# pad3.net
KiCad netlist of a schematic drawn in EAGLE
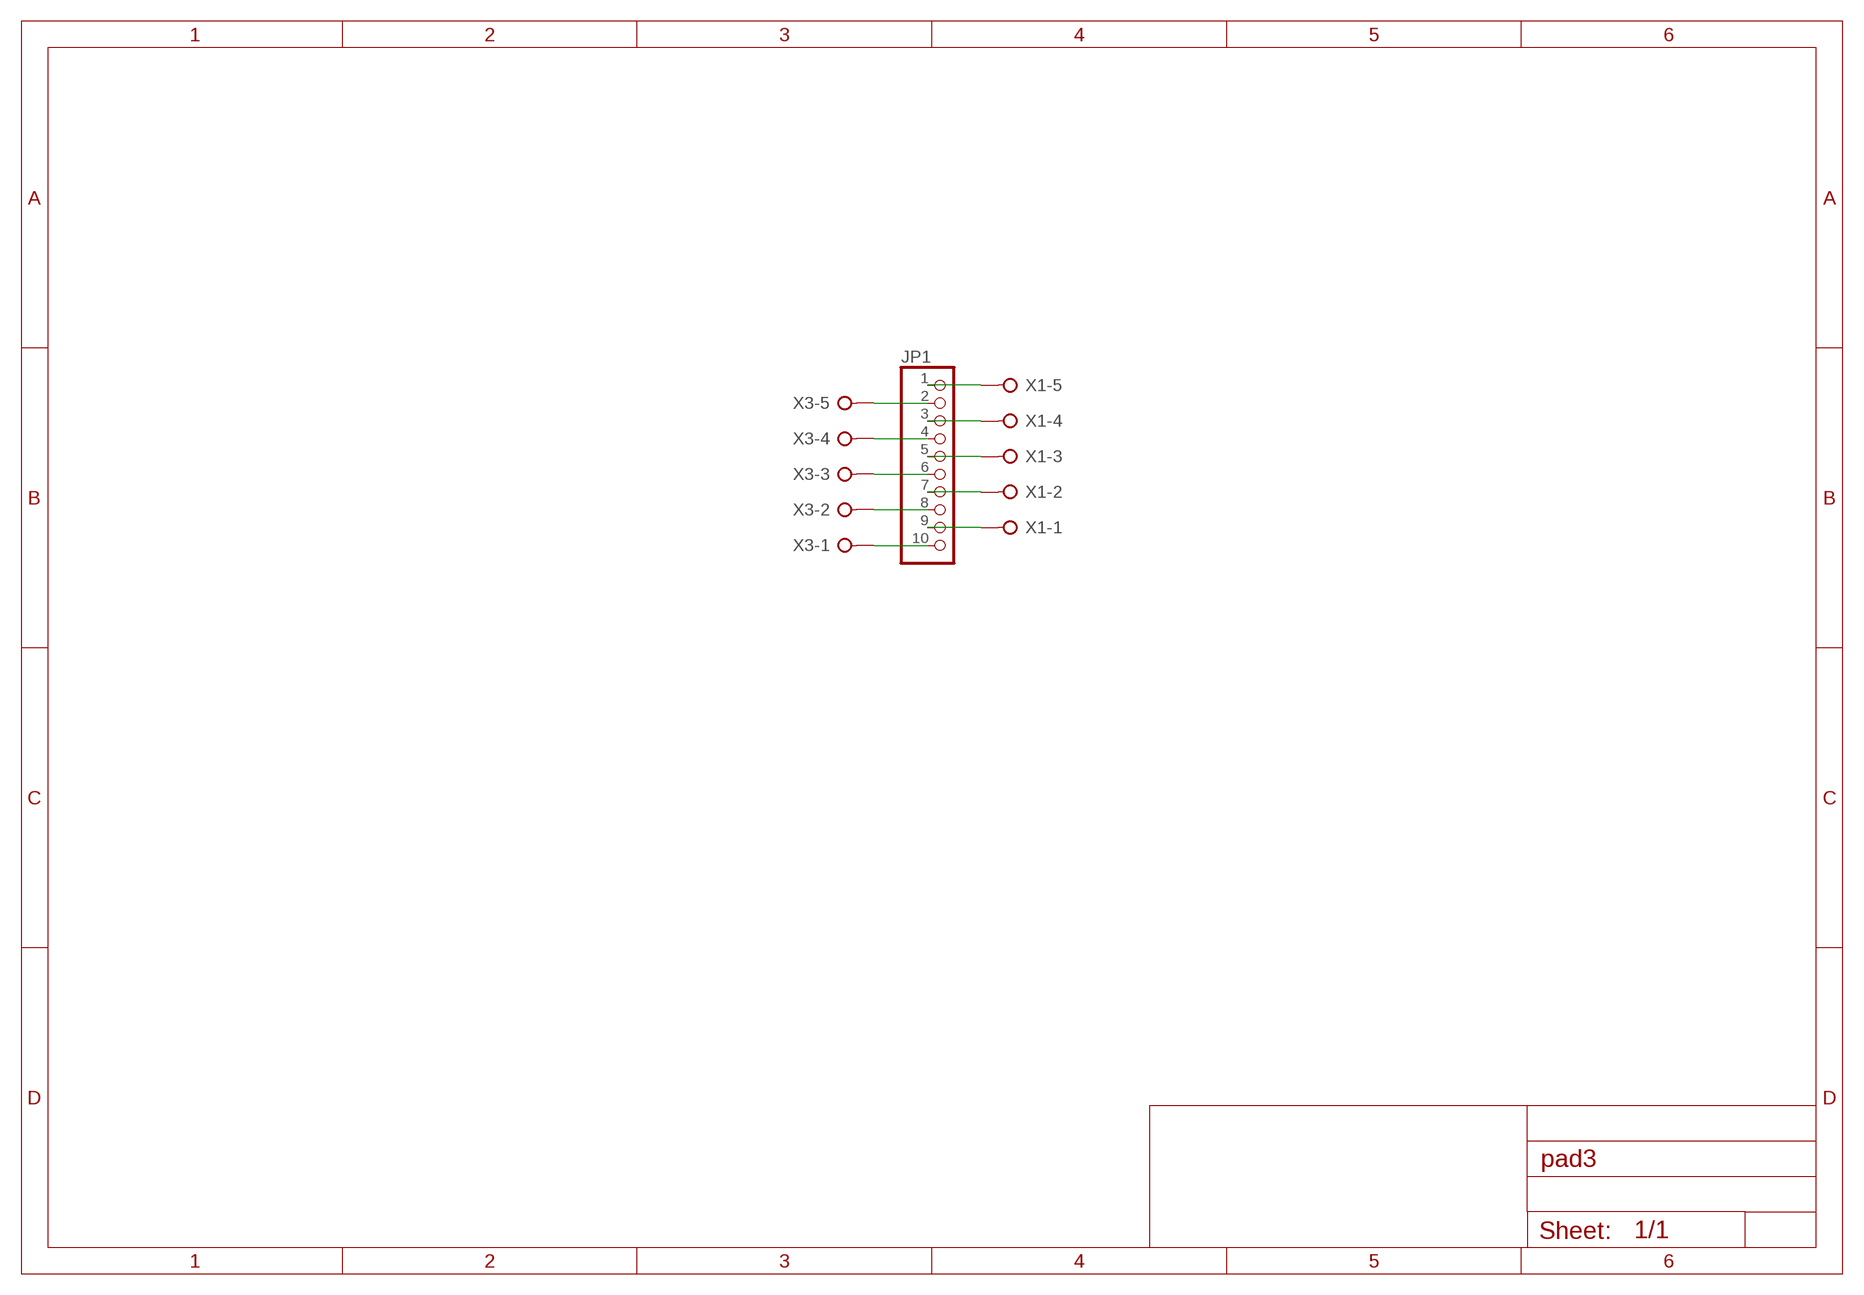
[diagram p0: schematic, sheet 1]

(export (version "E")
  (design (tool "Eeschema 10.0.6"))
  (components
    (comp (ref "JP1")
      (value "PINHD-1X10")
      (footprint "eagle-import:1X10")
      (libsource (lib "eagle-import") (part "PINHD-1X10"))
    )
    (comp (ref "X1")
      (value "W237-05P")
      (footprint "eagle-import:W237-5P")
      (libsource (lib "eagle-import") (part "W237-05P"))
    )
    (comp (ref "X3")
      (value "W237-05P")
      (footprint "eagle-import:W237-5P")
      (libsource (lib "eagle-import") (part "W237-05P"))
    )
  )
  (nets
    (net (code "1") (name "Net-(X1A-KL)") (class "Default")
      (node (ref "JP1") (pin "9") (pinfunction "9_9") (pintype "passive"))
      (node (ref "X1") (pin "1") (pinfunction "KL_1") (pintype "passive"))
    )
    (net (code "2") (name "Net-(X1B-KL)") (class "Default")
      (node (ref "JP1") (pin "7") (pinfunction "7_7") (pintype "passive"))
      (node (ref "X1") (pin "2") (pinfunction "KL_2") (pintype "passive"))
    )
    (net (code "3") (name "Net-(X1C-KL)") (class "Default")
      (node (ref "JP1") (pin "5") (pinfunction "5_5") (pintype "passive"))
      (node (ref "X1") (pin "3") (pinfunction "KL_3") (pintype "passive"))
    )
    (net (code "4") (name "Net-(X1D-KL)") (class "Default")
      (node (ref "JP1") (pin "3") (pinfunction "3_3") (pintype "passive"))
      (node (ref "X1") (pin "4") (pinfunction "KL_4") (pintype "passive"))
    )
    (net (code "5") (name "Net-(X1E-KL)") (class "Default")
      (node (ref "JP1") (pin "1") (pinfunction "1_1") (pintype "passive"))
      (node (ref "X1") (pin "5") (pinfunction "KL_5") (pintype "passive"))
    )
    (net (code "6") (name "Net-(X3A-KL)") (class "Default")
      (node (ref "JP1") (pin "10") (pinfunction "10_10") (pintype "passive"))
      (node (ref "X3") (pin "1") (pinfunction "KL_1") (pintype "passive"))
    )
    (net (code "7") (name "Net-(X3B-KL)") (class "Default")
      (node (ref "JP1") (pin "8") (pinfunction "8_8") (pintype "passive"))
      (node (ref "X3") (pin "2") (pinfunction "KL_2") (pintype "passive"))
    )
    (net (code "8") (name "Net-(X3C-KL)") (class "Default")
      (node (ref "JP1") (pin "6") (pinfunction "6_6") (pintype "passive"))
      (node (ref "X3") (pin "3") (pinfunction "KL_3") (pintype "passive"))
    )
    (net (code "9") (name "Net-(X3D-KL)") (class "Default")
      (node (ref "JP1") (pin "4") (pinfunction "4_4") (pintype "passive"))
      (node (ref "X3") (pin "4") (pinfunction "KL_4") (pintype "passive"))
    )
    (net (code "10") (name "Net-(X3E-KL)") (class "Default")
      (node (ref "JP1") (pin "2") (pinfunction "2_2") (pintype "passive"))
      (node (ref "X3") (pin "5") (pinfunction "KL_5") (pintype "passive"))
    )
  )
)
